# B4_FM_-X_SOLAR_PANEL_v2.net
KiCad netlist of a schematic drawn in EAGLE
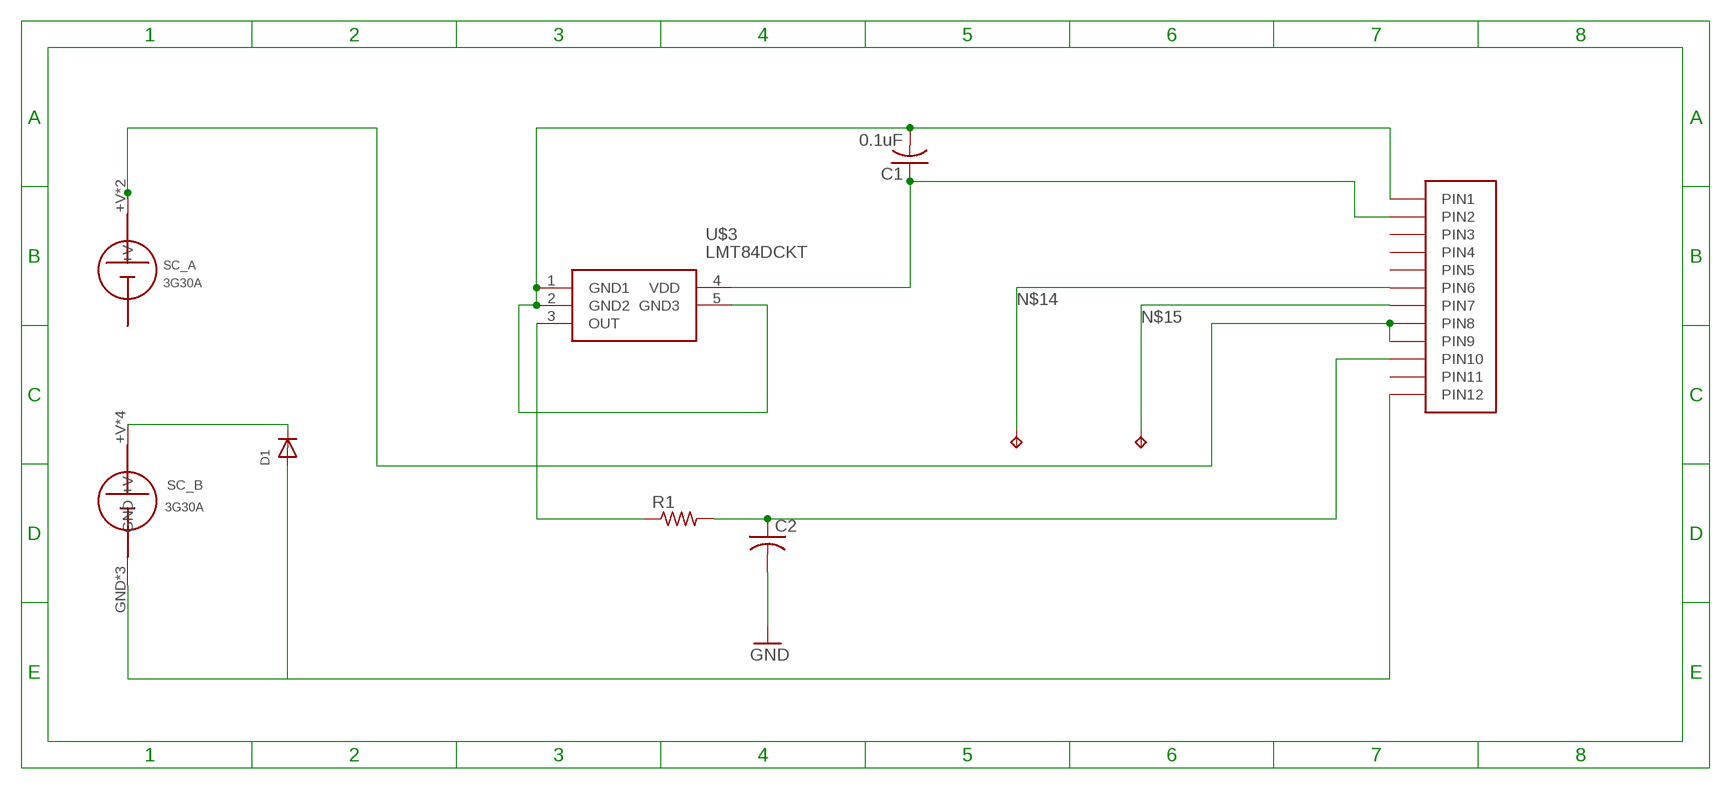
[diagram p0: schematic, sheet 1]

(export (version "E")
  (design (tool "Eeschema 10.0.6"))
  (components
    (comp (ref "C1")
      (value "0.1uF")
      (footprint "eagle-import:C0805")
      (libsource (lib "eagle-import") (part "C-USC0805"))
    )
    (comp (ref "C2")
      (value "C-USC0805")
      (footprint "eagle-import:C0805")
      (libsource (lib "eagle-import") (part "C-USC0805"))
    )
    (comp (ref "D1")
      (value "DIODE_SOD-123FL")
      (footprint "eagle-import:SOD-123FL")
      (libsource (lib "eagle-import") (part "DIODE_SOD-123FL"))
    )
    (comp (ref "R1")
      (value "R-US_R0402")
      (footprint "eagle-import:R0402")
      (libsource (lib "eagle-import") (part "R-US_R0402"))
    )
    (comp (ref "SDA1")
      (value "S1751-46R")
      (footprint "eagle-import:S1751-46R")
      (libsource (lib "eagle-import") (part "S1751-46R"))
    )
    (comp (ref "SDA3")
      (value "S1751-46R")
      (footprint "eagle-import:S1751-46R")
      (libsource (lib "eagle-import") (part "S1751-46R"))
    )
    (comp (ref "SOLARCELL_A")
      (value "SC_A")
      (footprint "eagle-import:SC_A")
      (libsource (lib "eagle-import") (part "SC_A"))
    )
    (comp (ref "SOLARCELL_B")
      (value "SC_B")
      (footprint "eagle-import:SC_B")
      (libsource (lib "eagle-import") (part "SC_B"))
    )
    (comp (ref "U$1")
      (value "HEADER12PIN")
      (footprint "eagle-import:HEADER12PIN")
      (libsource (lib "eagle-import") (part "HEADER12PIN"))
    )
    (comp (ref "U$3")
      (value "LMT84DCKT")
      (footprint "eagle-import:SOT65P210X110-5N")
      (fields (field (name "RS_PART_NUMBER") "8115860"))
      (libsource (lib "eagle-import") (part "LMT84DCKT"))
    )
  )
  (nets
    (net (code "1") (name "/N$14") (class "Default")
      (node (ref "SDA1") (pin "P$1") (pinfunction "TP_P$1") (pintype "input"))
      (node (ref "U$1") (pin "P6") (pinfunction "PIN6_P6") (pintype "bidirectional"))
    )
    (net (code "2") (name "/N$15") (class "Default")
      (node (ref "SDA3") (pin "P$1") (pinfunction "TP_P$1") (pintype "input"))
      (node (ref "U$1") (pin "P7") (pinfunction "PIN7_P7") (pintype "bidirectional"))
    )
    (net (code "3") (name "GND") (class "Default")
      (node (ref "C1") (pin "2") (pinfunction "2_2") (pintype "passive"))
      (node (ref "C2") (pin "2") (pinfunction "2_2") (pintype "passive"))
      (node (ref "D1") (pin "A") (pinfunction "A_A") (pintype "passive"))
      (node (ref "SOLARCELL_B") (pin "GND") (pinfunction "GND_GND") (pintype "bidirectional"))
      (node (ref "SOLARCELL_B") (pin "GND1") (pinfunction "GND_GND1") (pintype "bidirectional"))
      (node (ref "SOLARCELL_B") (pin "GND2") (pinfunction "GND_GND2") (pintype "bidirectional"))
      (node (ref "U$1") (pin "P1") (pinfunction "PIN1_P1") (pintype "bidirectional"))
      (node (ref "U$1") (pin "P12") (pinfunction "PIN12_P12") (pintype "bidirectional"))
      (node (ref "U$3") (pin "1") (pinfunction "GND1_1") (pintype "power_in"))
      (node (ref "U$3") (pin "2") (pinfunction "GND2_2") (pintype "power_in"))
      (node (ref "U$3") (pin "5") (pinfunction "GND3_5") (pintype "power_in"))
    )
    (net (code "4") (name "Net-(D1-PadC)") (class "Default")
      (node (ref "D1") (pin "C") (pinfunction "C_C") (pintype "passive"))
      (node (ref "SOLARCELL_B") (pin "+V") (pinfunction "+V_+V") (pintype "bidirectional"))
      (node (ref "SOLARCELL_B") (pin "+V2") (pinfunction "+V_+V2") (pintype "bidirectional"))
      (node (ref "SOLARCELL_B") (pin "+V3") (pinfunction "+V_+V3") (pintype "bidirectional"))
      (node (ref "SOLARCELL_B") (pin "+V4") (pinfunction "+V_+V4") (pintype "bidirectional"))
    )
    (net (code "5") (name "Net-(U$1-PIN2)") (class "Default")
      (node (ref "C1") (pin "1") (pinfunction "1_1") (pintype "passive"))
      (node (ref "U$1") (pin "P2") (pinfunction "PIN2_P2") (pintype "bidirectional"))
      (node (ref "U$3") (pin "4") (pinfunction "VDD_4") (pintype "power_in"))
    )
    (net (code "6") (name "Net-(U$1-PIN8)") (class "Default")
      (node (ref "SOLARCELL_A") (pin "+V") (pinfunction "+V_+V") (pintype "bidirectional"))
      (node (ref "SOLARCELL_A") (pin "+V1") (pinfunction "+V_+V1") (pintype "bidirectional"))
      (node (ref "U$1") (pin "P8") (pinfunction "PIN8_P8") (pintype "bidirectional"))
      (node (ref "U$1") (pin "P9") (pinfunction "PIN9_P9") (pintype "bidirectional"))
    )
    (net (code "7") (name "Net-(U$1-PIN10)") (class "Default")
      (node (ref "C2") (pin "1") (pinfunction "1_1") (pintype "passive"))
      (node (ref "R1") (pin "2") (pinfunction "2_2") (pintype "passive"))
      (node (ref "U$1") (pin "P10") (pinfunction "PIN10_P10") (pintype "bidirectional"))
    )
    (net (code "8") (name "Net-(U$3-OUT)") (class "Default")
      (node (ref "R1") (pin "1") (pinfunction "1_1") (pintype "passive"))
      (node (ref "U$3") (pin "3") (pinfunction "OUT_3") (pintype "output"))
    )
    (net (code "9") (name "unconnected-(U$1-PIN3-PadP3)") (class "Default")
      (node (ref "U$1") (pin "P3") (pinfunction "PIN3_P3") (pintype "bidirectional"))
    )
    (net (code "10") (name "unconnected-(U$1-PIN4-PadP4)") (class "Default")
      (node (ref "U$1") (pin "P4") (pinfunction "PIN4_P4") (pintype "bidirectional"))
    )
    (net (code "11") (name "unconnected-(U$1-PIN5-PadP5)") (class "Default")
      (node (ref "U$1") (pin "P5") (pinfunction "PIN5_P5") (pintype "bidirectional"))
    )
    (net (code "12") (name "unconnected-(U$1-PIN11-PadP11)") (class "Default")
      (node (ref "U$1") (pin "P11") (pinfunction "PIN11_P11") (pintype "bidirectional"))
    )
  )
)
